# Central_Board.net
KiCad netlist of a schematic drawn in EAGLE
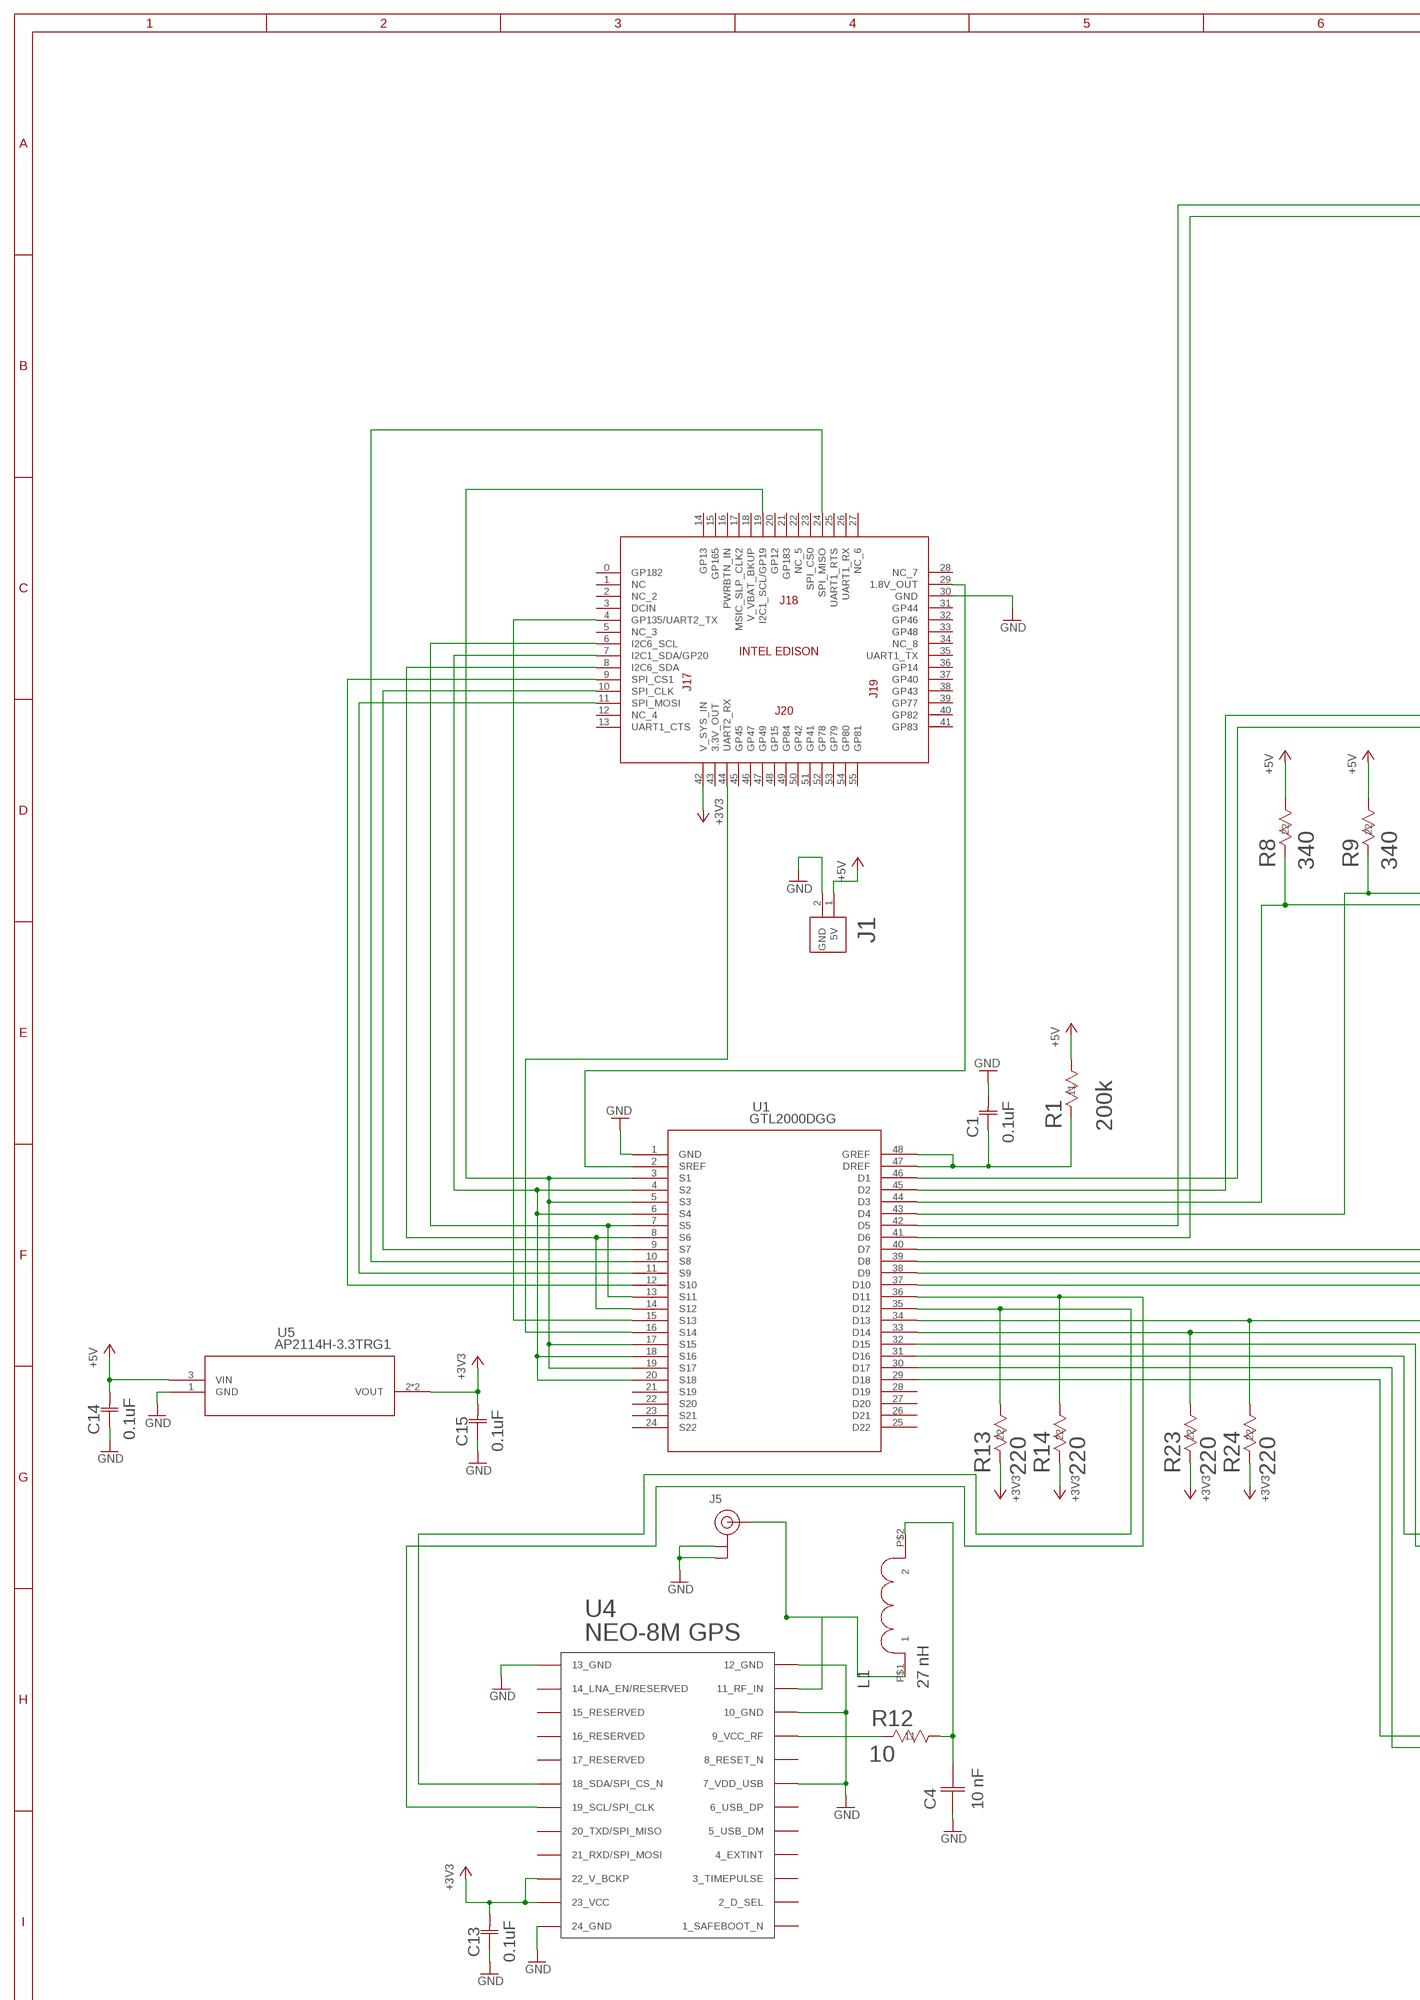
[diagram p0: schematic, sheet 1, part 1 of 2]
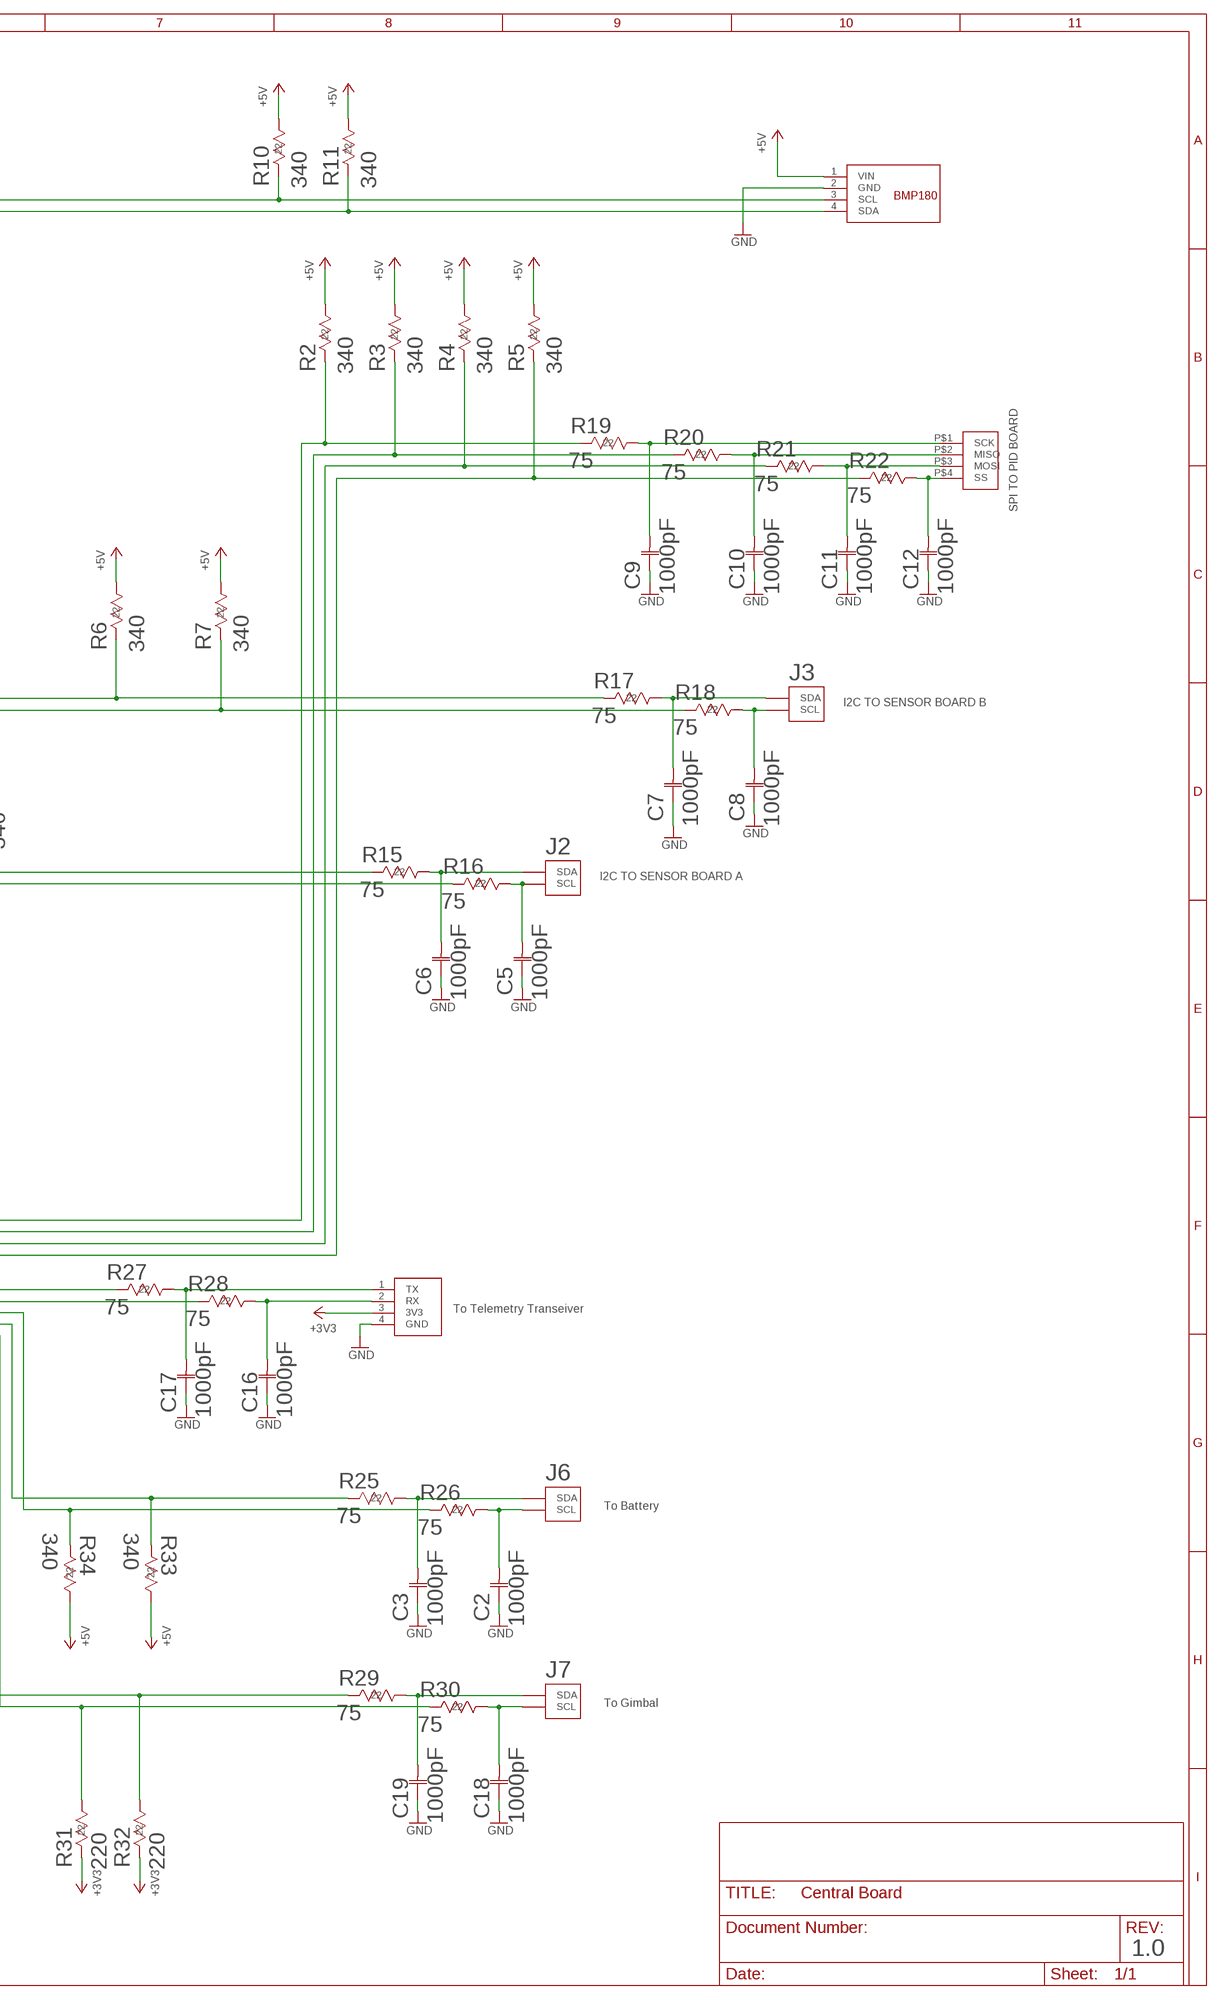
[diagram p1: schematic, sheet 1, part 2 of 2]

(export (version "E")
  (design (tool "Eeschema 10.0.6"))
  (components
    (comp (ref "C1")
      (value "0.1uF")
      (footprint "eagle-import:0805")
      (fields (field (name "MANUFACTURER_PART_NUMBER") "08055C104KAT2A"))
      (libsource (lib "eagle-import") (part "08055C104KAT2A"))
    )
    (comp (ref "C2")
      (value "1000pF")
      (footprint "eagle-import:G-155-M")
      (fields (field (name "MANUFACTURER_PART_NUMBER") "GRM155R60J102KA01D"))
      (libsource (lib "eagle-import") (part "GRM155R60J102KA01DG-155-M"))
    )
    (comp (ref "C3")
      (value "1000pF")
      (footprint "eagle-import:G-155-M")
      (fields (field (name "MANUFACTURER_PART_NUMBER") "GRM155R60J102KA01D"))
      (libsource (lib "eagle-import") (part "GRM155R60J102KA01DG-155-M"))
    )
    (comp (ref "C4")
      (value "10 nF")
      (footprint "eagle-import:0603_CAPACITOR")
      (libsource (lib "eagle-import") (part "10NF_CAPACITOR"))
    )
    (comp (ref "C5")
      (value "1000pF")
      (footprint "eagle-import:G-155-M")
      (fields (field (name "MANUFACTURER_PART_NUMBER") "GRM155R60J102KA01D"))
      (libsource (lib "eagle-import") (part "GRM155R60J102KA01DG-155-M"))
    )
    (comp (ref "C6")
      (value "1000pF")
      (footprint "eagle-import:G-155-M")
      (fields (field (name "MANUFACTURER_PART_NUMBER") "GRM155R60J102KA01D"))
      (libsource (lib "eagle-import") (part "GRM155R60J102KA01DG-155-M"))
    )
    (comp (ref "C7")
      (value "1000pF")
      (footprint "eagle-import:G-155-M")
      (fields (field (name "MANUFACTURER_PART_NUMBER") "GRM155R60J102KA01D"))
      (libsource (lib "eagle-import") (part "GRM155R60J102KA01DG-155-M"))
    )
    (comp (ref "C8")
      (value "1000pF")
      (footprint "eagle-import:G-155-M")
      (fields (field (name "MANUFACTURER_PART_NUMBER") "GRM155R60J102KA01D"))
      (libsource (lib "eagle-import") (part "GRM155R60J102KA01DG-155-M"))
    )
    (comp (ref "C9")
      (value "1000pF")
      (footprint "eagle-import:G-155-M")
      (fields (field (name "MANUFACTURER_PART_NUMBER") "GRM155R60J102KA01D"))
      (libsource (lib "eagle-import") (part "GRM155R60J102KA01DG-155-M"))
    )
    (comp (ref "C10")
      (value "1000pF")
      (footprint "eagle-import:G-155-M")
      (fields (field (name "MANUFACTURER_PART_NUMBER") "GRM155R60J102KA01D"))
      (libsource (lib "eagle-import") (part "GRM155R60J102KA01DG-155-M"))
    )
    (comp (ref "C11")
      (value "1000pF")
      (footprint "eagle-import:G-155-M")
      (fields (field (name "MANUFACTURER_PART_NUMBER") "GRM155R60J102KA01D"))
      (libsource (lib "eagle-import") (part "GRM155R60J102KA01DG-155-M"))
    )
    (comp (ref "C12")
      (value "1000pF")
      (footprint "eagle-import:G-155-M")
      (fields (field (name "MANUFACTURER_PART_NUMBER") "GRM155R60J102KA01D"))
      (libsource (lib "eagle-import") (part "GRM155R60J102KA01DG-155-M"))
    )
    (comp (ref "C13")
      (value "0.1uF")
      (footprint "eagle-import:0805")
      (fields (field (name "MANUFACTURER_PART_NUMBER") "08055C104KAT2A"))
      (libsource (lib "eagle-import") (part "08055C104KAT2A"))
    )
    (comp (ref "C14")
      (value "0.1uF")
      (footprint "eagle-import:0805")
      (fields (field (name "MANUFACTURER_PART_NUMBER") "08055C104KAT2A"))
      (libsource (lib "eagle-import") (part "08055C104KAT2A"))
    )
    (comp (ref "C15")
      (value "0.1uF")
      (footprint "eagle-import:0805")
      (fields (field (name "MANUFACTURER_PART_NUMBER") "08055C104KAT2A"))
      (libsource (lib "eagle-import") (part "08055C104KAT2A"))
    )
    (comp (ref "C16")
      (value "1000pF")
      (footprint "eagle-import:G-155-M")
      (fields (field (name "MANUFACTURER_PART_NUMBER") "GRM155R60J102KA01D"))
      (libsource (lib "eagle-import") (part "GRM155R60J102KA01DG-155-M"))
    )
    (comp (ref "C17")
      (value "1000pF")
      (footprint "eagle-import:G-155-M")
      (fields (field (name "MANUFACTURER_PART_NUMBER") "GRM155R60J102KA01D"))
      (libsource (lib "eagle-import") (part "GRM155R60J102KA01DG-155-M"))
    )
    (comp (ref "C18")
      (value "1000pF")
      (footprint "eagle-import:G-155-M")
      (fields (field (name "MANUFACTURER_PART_NUMBER") "GRM155R60J102KA01D"))
      (libsource (lib "eagle-import") (part "GRM155R60J102KA01DG-155-M"))
    )
    (comp (ref "C19")
      (value "1000pF")
      (footprint "eagle-import:G-155-M")
      (fields (field (name "MANUFACTURER_PART_NUMBER") "GRM155R60J102KA01D"))
      (libsource (lib "eagle-import") (part "GRM155R60J102KA01DG-155-M"))
    )
    (comp (ref "J1")
      (value "POWER_CONNECTOR")
      (footprint "eagle-import:XH_CONNECTOR")
      (libsource (lib "eagle-import") (part "POWER_CONNECTOR"))
    )
    (comp (ref "J2")
      (value "I2C_CONNECTOR")
      (footprint "eagle-import:XH_CONNECTOR")
      (libsource (lib "eagle-import") (part "I2C_CONNECTOR"))
    )
    (comp (ref "J3")
      (value "I2C_CONNECTOR")
      (footprint "eagle-import:XH_CONNECTOR")
      (libsource (lib "eagle-import") (part "I2C_CONNECTOR"))
    )
    (comp (ref "J4")
      (value "SPI_CONNECTOR")
      (footprint "eagle-import:JST-XH_4POS")
      (libsource (lib "eagle-import") (part "SPI_CONNECTOR"))
    )
    (comp (ref "J5")
      (value "U.FL")
      (footprint "eagle-import:U.FL")
      (libsource (lib "eagle-import") (part "U.FL"))
    )
    (comp (ref "J6")
      (value "I2C_CONNECTOR")
      (footprint "eagle-import:XH_CONNECTOR")
      (libsource (lib "eagle-import") (part "I2C_CONNECTOR"))
    )
    (comp (ref "J7")
      (value "I2C_CONNECTOR")
      (footprint "eagle-import:XH_CONNECTOR")
      (libsource (lib "eagle-import") (part "I2C_CONNECTOR"))
    )
    (comp (ref "L1")
      (value "27 nH")
      (footprint "eagle-import:0402_INDUCTOR")
      (libsource (lib "eagle-import") (part "27NH_INDUCTOR"))
    )
    (comp (ref "R1")
      (value "200k")
      (footprint "eagle-import:STA_RMCF0603")
      (fields (field (name "MANUFACTURER_PART_NUMBER") "RMCF0603FT200K"))
      (libsource (lib "eagle-import") (part "RMCF0603FT200K"))
    )
    (comp (ref "R2")
      (value "340")
      (footprint "eagle-import:RC0603N")
      (fields
        (field (name "DIGIKEYPARTNUMBER") "311340HRTRND")
        (field (name "MANUFACTURER_PART_NUMBER") "RC0603FR07340RL")
        (field (name "NEWARKPARTNUMBER") "66R2325")
      )
      (libsource (lib "eagle-import") (part "RC0603FR-07340RL"))
    )
    (comp (ref "R3")
      (value "340")
      (footprint "eagle-import:RC0603N")
      (fields
        (field (name "DIGIKEYPARTNUMBER") "311340HRTRND")
        (field (name "MANUFACTURER_PART_NUMBER") "RC0603FR07340RL")
        (field (name "NEWARKPARTNUMBER") "66R2325")
      )
      (libsource (lib "eagle-import") (part "RC0603FR-07340RL"))
    )
    (comp (ref "R4")
      (value "340")
      (footprint "eagle-import:RC0603N")
      (fields
        (field (name "DIGIKEYPARTNUMBER") "311340HRTRND")
        (field (name "MANUFACTURER_PART_NUMBER") "RC0603FR07340RL")
        (field (name "NEWARKPARTNUMBER") "66R2325")
      )
      (libsource (lib "eagle-import") (part "RC0603FR-07340RL"))
    )
    (comp (ref "R5")
      (value "340")
      (footprint "eagle-import:RC0603N")
      (fields
        (field (name "DIGIKEYPARTNUMBER") "311340HRTRND")
        (field (name "MANUFACTURER_PART_NUMBER") "RC0603FR07340RL")
        (field (name "NEWARKPARTNUMBER") "66R2325")
      )
      (libsource (lib "eagle-import") (part "RC0603FR-07340RL"))
    )
    (comp (ref "R6")
      (value "340")
      (footprint "eagle-import:RC0603N")
      (fields
        (field (name "DIGIKEYPARTNUMBER") "311340HRTRND")
        (field (name "MANUFACTURER_PART_NUMBER") "RC0603FR07340RL")
        (field (name "NEWARKPARTNUMBER") "66R2325")
      )
      (libsource (lib "eagle-import") (part "RC0603FR-07340RL"))
    )
    (comp (ref "R7")
      (value "340")
      (footprint "eagle-import:RC0603N")
      (fields
        (field (name "DIGIKEYPARTNUMBER") "311340HRTRND")
        (field (name "MANUFACTURER_PART_NUMBER") "RC0603FR07340RL")
        (field (name "NEWARKPARTNUMBER") "66R2325")
      )
      (libsource (lib "eagle-import") (part "RC0603FR-07340RL"))
    )
    (comp (ref "R8")
      (value "340")
      (footprint "eagle-import:RC0603N")
      (fields
        (field (name "DIGIKEYPARTNUMBER") "311340HRTRND")
        (field (name "MANUFACTURER_PART_NUMBER") "RC0603FR07340RL")
        (field (name "NEWARKPARTNUMBER") "66R2325")
      )
      (libsource (lib "eagle-import") (part "RC0603FR-07340RL"))
    )
    (comp (ref "R9")
      (value "340")
      (footprint "eagle-import:RC0603N")
      (fields
        (field (name "DIGIKEYPARTNUMBER") "311340HRTRND")
        (field (name "MANUFACTURER_PART_NUMBER") "RC0603FR07340RL")
        (field (name "NEWARKPARTNUMBER") "66R2325")
      )
      (libsource (lib "eagle-import") (part "RC0603FR-07340RL"))
    )
    (comp (ref "R10")
      (value "340")
      (footprint "eagle-import:RC0603N")
      (fields
        (field (name "DIGIKEYPARTNUMBER") "311340HRTRND")
        (field (name "MANUFACTURER_PART_NUMBER") "RC0603FR07340RL")
        (field (name "NEWARKPARTNUMBER") "66R2325")
      )
      (libsource (lib "eagle-import") (part "RC0603FR-07340RL"))
    )
    (comp (ref "R11")
      (value "340")
      (footprint "eagle-import:RC0603N")
      (fields
        (field (name "DIGIKEYPARTNUMBER") "311340HRTRND")
        (field (name "MANUFACTURER_PART_NUMBER") "RC0603FR07340RL")
        (field (name "NEWARKPARTNUMBER") "66R2325")
      )
      (libsource (lib "eagle-import") (part "RC0603FR-07340RL"))
    )
    (comp (ref "R12")
      (value "10")
      (footprint "eagle-import:STA_RNCP0805-M")
      (fields (field (name "MANUFACTURER_PART_NUMBER") "RNCP0805FTD10R0"))
      (libsource (lib "eagle-import") (part "RNCP0805FTD10R0STA_RNCP0805-M"))
    )
    (comp (ref "R13")
      (value "220")
      (footprint "eagle-import:RC0603N-M")
      (fields
        (field (name "DIGIKEYPARTNUMBER") "311220GRTRND")
        (field (name "MANUFACTURER_PART_NUMBER") "RC0603JR07220RL")
        (field (name "NEWARKPARTNUMBER") "68R0170")
      )
      (libsource (lib "eagle-import") (part "RC0603JR-07220RLRC0603N-M"))
    )
    (comp (ref "R14")
      (value "220")
      (footprint "eagle-import:RC0603N-M")
      (fields
        (field (name "DIGIKEYPARTNUMBER") "311220GRTRND")
        (field (name "MANUFACTURER_PART_NUMBER") "RC0603JR07220RL")
        (field (name "NEWARKPARTNUMBER") "68R0170")
      )
      (libsource (lib "eagle-import") (part "RC0603JR-07220RLRC0603N-M"))
    )
    (comp (ref "R15")
      (value "75")
      (footprint "eagle-import:RC0402N-M")
      (fields
        (field (name "DIGIKEYPARTNUMBER") "31175JRTRND")
        (field (name "MANUFACTURER_PART_NUMBER") "RC0402JR0775RL")
        (field (name "NEWARKPARTNUMBER") "66R1890")
      )
      (libsource (lib "eagle-import") (part "RC0402JR-0775RLRC0402N-M"))
    )
    (comp (ref "R16")
      (value "75")
      (footprint "eagle-import:RC0402N-M")
      (fields
        (field (name "DIGIKEYPARTNUMBER") "31175JRTRND")
        (field (name "MANUFACTURER_PART_NUMBER") "RC0402JR0775RL")
        (field (name "NEWARKPARTNUMBER") "66R1890")
      )
      (libsource (lib "eagle-import") (part "RC0402JR-0775RLRC0402N-M"))
    )
    (comp (ref "R17")
      (value "75")
      (footprint "eagle-import:RC0402N-M")
      (fields
        (field (name "DIGIKEYPARTNUMBER") "31175JRTRND")
        (field (name "MANUFACTURER_PART_NUMBER") "RC0402JR0775RL")
        (field (name "NEWARKPARTNUMBER") "66R1890")
      )
      (libsource (lib "eagle-import") (part "RC0402JR-0775RLRC0402N-M"))
    )
    (comp (ref "R18")
      (value "75")
      (footprint "eagle-import:RC0402N-M")
      (fields
        (field (name "DIGIKEYPARTNUMBER") "31175JRTRND")
        (field (name "MANUFACTURER_PART_NUMBER") "RC0402JR0775RL")
        (field (name "NEWARKPARTNUMBER") "66R1890")
      )
      (libsource (lib "eagle-import") (part "RC0402JR-0775RLRC0402N-M"))
    )
    (comp (ref "R19")
      (value "75")
      (footprint "eagle-import:RC0402N-M")
      (fields
        (field (name "DIGIKEYPARTNUMBER") "31175JRTRND")
        (field (name "MANUFACTURER_PART_NUMBER") "RC0402JR0775RL")
        (field (name "NEWARKPARTNUMBER") "66R1890")
      )
      (libsource (lib "eagle-import") (part "RC0402JR-0775RLRC0402N-M"))
    )
    (comp (ref "R20")
      (value "75")
      (footprint "eagle-import:RC0402N-M")
      (fields
        (field (name "DIGIKEYPARTNUMBER") "31175JRTRND")
        (field (name "MANUFACTURER_PART_NUMBER") "RC0402JR0775RL")
        (field (name "NEWARKPARTNUMBER") "66R1890")
      )
      (libsource (lib "eagle-import") (part "RC0402JR-0775RLRC0402N-M"))
    )
    (comp (ref "R21")
      (value "75")
      (footprint "eagle-import:RC0402N-M")
      (fields
        (field (name "DIGIKEYPARTNUMBER") "31175JRTRND")
        (field (name "MANUFACTURER_PART_NUMBER") "RC0402JR0775RL")
        (field (name "NEWARKPARTNUMBER") "66R1890")
      )
      (libsource (lib "eagle-import") (part "RC0402JR-0775RLRC0402N-M"))
    )
    (comp (ref "R22")
      (value "75")
      (footprint "eagle-import:RC0402N-M")
      (fields
        (field (name "DIGIKEYPARTNUMBER") "31175JRTRND")
        (field (name "MANUFACTURER_PART_NUMBER") "RC0402JR0775RL")
        (field (name "NEWARKPARTNUMBER") "66R1890")
      )
      (libsource (lib "eagle-import") (part "RC0402JR-0775RLRC0402N-M"))
    )
    (comp (ref "R23")
      (value "220")
      (footprint "eagle-import:RC0603N-M")
      (fields
        (field (name "DIGIKEYPARTNUMBER") "311220GRTRND")
        (field (name "MANUFACTURER_PART_NUMBER") "RC0603JR07220RL")
        (field (name "NEWARKPARTNUMBER") "68R0170")
      )
      (libsource (lib "eagle-import") (part "RC0603JR-07220RLRC0603N-M"))
    )
    (comp (ref "R24")
      (value "220")
      (footprint "eagle-import:RC0603N-M")
      (fields
        (field (name "DIGIKEYPARTNUMBER") "311220GRTRND")
        (field (name "MANUFACTURER_PART_NUMBER") "RC0603JR07220RL")
        (field (name "NEWARKPARTNUMBER") "68R0170")
      )
      (libsource (lib "eagle-import") (part "RC0603JR-07220RLRC0603N-M"))
    )
    (comp (ref "R25")
      (value "75")
      (footprint "eagle-import:RC0402N-M")
      (fields
        (field (name "DIGIKEYPARTNUMBER") "31175JRTRND")
        (field (name "MANUFACTURER_PART_NUMBER") "RC0402JR0775RL")
        (field (name "NEWARKPARTNUMBER") "66R1890")
      )
      (libsource (lib "eagle-import") (part "RC0402JR-0775RLRC0402N-M"))
    )
    (comp (ref "R26")
      (value "75")
      (footprint "eagle-import:RC0402N-M")
      (fields
        (field (name "DIGIKEYPARTNUMBER") "31175JRTRND")
        (field (name "MANUFACTURER_PART_NUMBER") "RC0402JR0775RL")
        (field (name "NEWARKPARTNUMBER") "66R1890")
      )
      (libsource (lib "eagle-import") (part "RC0402JR-0775RLRC0402N-M"))
    )
    (comp (ref "R27")
      (value "75")
      (footprint "eagle-import:RC0402N-M")
      (fields
        (field (name "DIGIKEYPARTNUMBER") "31175JRTRND")
        (field (name "MANUFACTURER_PART_NUMBER") "RC0402JR0775RL")
        (field (name "NEWARKPARTNUMBER") "66R1890")
      )
      (libsource (lib "eagle-import") (part "RC0402JR-0775RLRC0402N-M"))
    )
    (comp (ref "R28")
      (value "75")
      (footprint "eagle-import:RC0402N-M")
      (fields
        (field (name "DIGIKEYPARTNUMBER") "31175JRTRND")
        (field (name "MANUFACTURER_PART_NUMBER") "RC0402JR0775RL")
        (field (name "NEWARKPARTNUMBER") "66R1890")
      )
      (libsource (lib "eagle-import") (part "RC0402JR-0775RLRC0402N-M"))
    )
    (comp (ref "R29")
      (value "75")
      (footprint "eagle-import:RC0402N-M")
      (fields
        (field (name "DIGIKEYPARTNUMBER") "31175JRTRND")
        (field (name "MANUFACTURER_PART_NUMBER") "RC0402JR0775RL")
        (field (name "NEWARKPARTNUMBER") "66R1890")
      )
      (libsource (lib "eagle-import") (part "RC0402JR-0775RLRC0402N-M"))
    )
    (comp (ref "R30")
      (value "75")
      (footprint "eagle-import:RC0402N-M")
      (fields
        (field (name "DIGIKEYPARTNUMBER") "31175JRTRND")
        (field (name "MANUFACTURER_PART_NUMBER") "RC0402JR0775RL")
        (field (name "NEWARKPARTNUMBER") "66R1890")
      )
      (libsource (lib "eagle-import") (part "RC0402JR-0775RLRC0402N-M"))
    )
    (comp (ref "R31")
      (value "220")
      (footprint "eagle-import:RC0603N-M")
      (fields
        (field (name "DIGIKEYPARTNUMBER") "311220GRTRND")
        (field (name "MANUFACTURER_PART_NUMBER") "RC0603JR07220RL")
        (field (name "NEWARKPARTNUMBER") "68R0170")
      )
      (libsource (lib "eagle-import") (part "RC0603JR-07220RLRC0603N-M"))
    )
    (comp (ref "R32")
      (value "220")
      (footprint "eagle-import:RC0603N-M")
      (fields
        (field (name "DIGIKEYPARTNUMBER") "311220GRTRND")
        (field (name "MANUFACTURER_PART_NUMBER") "RC0603JR07220RL")
        (field (name "NEWARKPARTNUMBER") "68R0170")
      )
      (libsource (lib "eagle-import") (part "RC0603JR-07220RLRC0603N-M"))
    )
    (comp (ref "R33")
      (value "340")
      (footprint "eagle-import:RC0603N")
      (fields
        (field (name "DIGIKEYPARTNUMBER") "311340HRTRND")
        (field (name "MANUFACTURER_PART_NUMBER") "RC0603FR07340RL")
        (field (name "NEWARKPARTNUMBER") "66R2325")
      )
      (libsource (lib "eagle-import") (part "RC0603FR-07340RL"))
    )
    (comp (ref "R34")
      (value "340")
      (footprint "eagle-import:RC0603N")
      (fields
        (field (name "DIGIKEYPARTNUMBER") "311340HRTRND")
        (field (name "MANUFACTURER_PART_NUMBER") "RC0603FR07340RL")
        (field (name "NEWARKPARTNUMBER") "66R2325")
      )
      (libsource (lib "eagle-import") (part "RC0603FR-07340RL"))
    )
    (comp (ref "U$1")
      (value "4_PIN_TELE_CONNECTOR")
      (footprint "eagle-import:4_PIN_TELE_CONNECTOR")
      (libsource (lib "eagle-import") (part "4_PIN_TELE_CONNECTOR"))
    )
    (comp (ref "U1")
      (value "GTL2000DGG")
      (footprint "eagle-import:SOT362-1")
      (libsource (lib "eagle-import") (part "GTL2000DGG"))
    )
    (comp (ref "U3")
      (value "INTEL_EDISON")
      (footprint "eagle-import:INTEL_EDISON")
      (libsource (lib "eagle-import") (part "INTEL_EDISON"))
    )
    (comp (ref "U4")
      (value "NEO-M8")
      (footprint "eagle-import:NEO-M8")
      (libsource (lib "eagle-import") (part "NEO-M8"))
    )
    (comp (ref "U5")
      (value "AP2114H-3.3TRG1")
      (footprint "eagle-import:SOT-223")
      (fields (field (name "MANUFACTURER_PART_NUMBER") "ap2114h3.3trg1"))
      (libsource (lib "eagle-import") (part "AP2114H-3.3TRG1"))
    )
    (comp (ref "U9")
      (value "BMP180_BARO")
      (footprint "eagle-import:BMP180_BARO")
      (libsource (lib "eagle-import") (part "BMP180_BARO"))
    )
  )
  (nets
    (net (code "1") (name "+3V3") (class "Default")
      (node (ref "C13") (pin "2") (pinfunction "2_2") (pintype "passive"))
      (node (ref "C15") (pin "2") (pinfunction "2_2") (pintype "passive"))
      (node (ref "R13") (pin "2") (pinfunction "22_2") (pintype "passive"))
      (node (ref "R14") (pin "2") (pinfunction "22_2") (pintype "passive"))
      (node (ref "R23") (pin "2") (pinfunction "22_2") (pintype "passive"))
      (node (ref "R24") (pin "2") (pinfunction "22_2") (pintype "passive"))
      (node (ref "R31") (pin "2") (pinfunction "22_2") (pintype "passive"))
      (node (ref "R32") (pin "2") (pinfunction "22_2") (pintype "passive"))
      (node (ref "U$1") (pin "3") (pinfunction "3V3_3") (pintype "bidirectional"))
      (node (ref "U3") (pin "42") (pinfunction "V_SYS_IN_42") (pintype "power_in"))
      (node (ref "U4") (pin "22") (pinfunction "22_V_BCKP_22") (pintype "bidirectional"))
      (node (ref "U4") (pin "23") (pinfunction "23_VCC_23") (pintype "bidirectional"))
      (node (ref "U5") (pin "2") (pinfunction "VOUT_2") (pintype "output"))
      (node (ref "U5") (pin "4") (pinfunction "VOUT_4") (pintype "output"))
    )
    (net (code "2") (name "+5V") (class "Default")
      (node (ref "C14") (pin "2") (pinfunction "2_2") (pintype "passive"))
      (node (ref "J1") (pin "1") (pinfunction "5V_1") (pintype "power_in"))
      (node (ref "R1") (pin "2") (pinfunction "22_2") (pintype "passive"))
      (node (ref "R10") (pin "1") (pinfunction "11_1") (pintype "passive"))
      (node (ref "R11") (pin "1") (pinfunction "11_1") (pintype "passive"))
      (node (ref "R2") (pin "1") (pinfunction "11_1") (pintype "passive"))
      (node (ref "R3") (pin "1") (pinfunction "11_1") (pintype "passive"))
      (node (ref "R33") (pin "1") (pinfunction "11_1") (pintype "passive"))
      (node (ref "R34") (pin "1") (pinfunction "11_1") (pintype "passive"))
      (node (ref "R4") (pin "1") (pinfunction "11_1") (pintype "passive"))
      (node (ref "R5") (pin "1") (pinfunction "11_1") (pintype "passive"))
      (node (ref "R6") (pin "1") (pinfunction "11_1") (pintype "passive"))
      (node (ref "R7") (pin "1") (pinfunction "11_1") (pintype "passive"))
      (node (ref "R8") (pin "1") (pinfunction "11_1") (pintype "passive"))
      (node (ref "R9") (pin "1") (pinfunction "11_1") (pintype "passive"))
      (node (ref "U5") (pin "3") (pinfunction "VIN_3") (pintype "input"))
      (node (ref "U9") (pin "1") (pinfunction "VIN_1") (pintype "power_in"))
    )
    (net (code "3") (name "/3.3V_OUT") (class "Default")
      (node (ref "U3") (pin "43") (pinfunction "3.3V_OUT_43") (pintype "power_in"))
    )
    (net (code "4") (name "/DCIN") (class "Default")
      (node (ref "U3") (pin "3") (pinfunction "DCIN_3") (pintype "power_in"))
    )
    (net (code "5") (name "/MSIC_SLP_CLK2") (class "Default")
      (node (ref "U3") (pin "17") (pinfunction "MSIC_SLP_CLK2_17") (pintype "power_in"))
    )
    (net (code "6") (name "/PWRBTN_IN") (class "Default")
      (node (ref "U3") (pin "16") (pinfunction "PWRBTN_IN_16") (pintype "power_in"))
    )
    (net (code "7") (name "/V_VBAT_BKUP") (class "Default")
      (node (ref "U3") (pin "18") (pinfunction "V_VBAT_BKUP_18") (pintype "power_in"))
    )
    (net (code "8") (name "GND") (class "Default")
      (node (ref "C1") (pin "2") (pinfunction "2_2") (pintype "passive"))
      (node (ref "C10") (pin "1") (pinfunction "11_1") (pintype "passive"))
      (node (ref "C11") (pin "1") (pinfunction "11_1") (pintype "passive"))
      (node (ref "C12") (pin "1") (pinfunction "11_1") (pintype "passive"))
      (node (ref "C13") (pin "1") (pinfunction "1_1") (pintype "passive"))
      (node (ref "C14") (pin "1") (pinfunction "1_1") (pintype "passive"))
      (node (ref "C15") (pin "1") (pinfunction "1_1") (pintype "passive"))
      (node (ref "C16") (pin "1") (pinfunction "11_1") (pintype "passive"))
      (node (ref "C17") (pin "1") (pinfunction "11_1") (pintype "passive"))
      (node (ref "C18") (pin "1") (pinfunction "11_1") (pintype "passive"))
      (node (ref "C19") (pin "1") (pinfunction "11_1") (pintype "passive"))
      (node (ref "C2") (pin "1") (pinfunction "11_1") (pintype "passive"))
      (node (ref "C3") (pin "1") (pinfunction "11_1") (pintype "passive"))
      (node (ref "C4") (pin "1") (pinfunction "1_1") (pintype "bidirectional"))
      (node (ref "C5") (pin "1") (pinfunction "11_1") (pintype "passive"))
      (node (ref "C6") (pin "1") (pinfunction "11_1") (pintype "passive"))
      (node (ref "C7") (pin "1") (pinfunction "11_1") (pintype "passive"))
      (node (ref "C8") (pin "1") (pinfunction "11_1") (pintype "passive"))
      (node (ref "C9") (pin "1") (pinfunction "11_1") (pintype "passive"))
      (node (ref "J1") (pin "2") (pinfunction "GND_2") (pintype "power_in"))
      (node (ref "J5") (pin "P$1") (pinfunction "GND_P$1") (pintype "bidirectional"))
      (node (ref "J5") (pin "P$2") (pinfunction "GND_P$2") (pintype "bidirectional"))
      (node (ref "U$1") (pin "4") (pinfunction "GND_4") (pintype "bidirectional"))
      (node (ref "U1") (pin "1") (pinfunction "GND_1") (pintype "passive"))
      (node (ref "U3") (pin "30") (pinfunction "GND_30") (pintype "power_in"))
      (node (ref "U4") (pin "10") (pinfunction "10_GND_10") (pintype "bidirectional"))
      (node (ref "U4") (pin "12") (pinfunction "12_GND_12") (pintype "bidirectional"))
      (node (ref "U4") (pin "13") (pinfunction "13_GND_13") (pintype "bidirectional"))
      (node (ref "U4") (pin "24") (pinfunction "24_GND_24") (pintype "bidirectional"))
      (node (ref "U4") (pin "7") (pinfunction "7_VDD_USB_7") (pintype "bidirectional"))
      (node (ref "U5") (pin "1") (pinfunction "GND_1") (pintype "power_in"))
      (node (ref "U9") (pin "2") (pinfunction "GND_2") (pintype "power_in"))
    )
    (net (code "9") (name "Net-(C2-22)") (class "Default")
      (node (ref "C2") (pin "2") (pinfunction "22_2") (pintype "passive"))
      (node (ref "J6") (pin "1") (pinfunction "SCL_1") (pintype "bidirectional"))
      (node (ref "R26") (pin "1") (pinfunction "11_1") (pintype "passive"))
    )
    (net (code "10") (name "Net-(C3-22)") (class "Default")
      (node (ref "C3") (pin "2") (pinfunction "22_2") (pintype "passive"))
      (node (ref "J6") (pin "2") (pinfunction "SDA_2") (pintype "bidirectional"))
      (node (ref "R25") (pin "1") (pinfunction "11_1") (pintype "passive"))
    )
    (net (code "11") (name "Net-(C5-22)") (class "Default")
      (node (ref "C5") (pin "2") (pinfunction "22_2") (pintype "passive"))
      (node (ref "J2") (pin "1") (pinfunction "SCL_1") (pintype "bidirectional"))
      (node (ref "R16") (pin "1") (pinfunction "11_1") (pintype "passive"))
    )
    (net (code "12") (name "Net-(C6-22)") (class "Default")
      (node (ref "C6") (pin "2") (pinfunction "22_2") (pintype "passive"))
      (node (ref "J2") (pin "2") (pinfunction "SDA_2") (pintype "bidirectional"))
      (node (ref "R15") (pin "1") (pinfunction "11_1") (pintype "passive"))
    )
    (net (code "13") (name "Net-(C7-22)") (class "Default")
      (node (ref "C7") (pin "2") (pinfunction "22_2") (pintype "passive"))
      (node (ref "J3") (pin "2") (pinfunction "SDA_2") (pintype "bidirectional"))
      (node (ref "R17") (pin "1") (pinfunction "11_1") (pintype "passive"))
    )
    (net (code "14") (name "Net-(C8-22)") (class "Default")
      (node (ref "C8") (pin "2") (pinfunction "22_2") (pintype "passive"))
      (node (ref "J3") (pin "1") (pinfunction "SCL_1") (pintype "bidirectional"))
      (node (ref "R18") (pin "1") (pinfunction "11_1") (pintype "passive"))
    )
    (net (code "15") (name "Net-(C9-22)") (class "Default")
      (node (ref "C9") (pin "2") (pinfunction "22_2") (pintype "passive"))
      (node (ref "J4") (pin "P$1") (pinfunction "SCK_P$1") (pintype "bidirectional"))
      (node (ref "R19") (pin "1") (pinfunction "11_1") (pintype "passive"))
    )
    (net (code "16") (name "Net-(C10-22)") (class "Default")
      (node (ref "C10") (pin "2") (pinfunction "22_2") (pintype "passive"))
      (node (ref "J4") (pin "P$2") (pinfunction "MISO_P$2") (pintype "bidirectional"))
      (node (ref "R20") (pin "1") (pinfunction "11_1") (pintype "passive"))
    )
    (net (code "17") (name "Net-(C11-22)") (class "Default")
      (node (ref "C11") (pin "2") (pinfunction "22_2") (pintype "passive"))
      (node (ref "J4") (pin "P$3") (pinfunction "MOSI_P$3") (pintype "bidirectional"))
      (node (ref "R21") (pin "1") (pinfunction "11_1") (pintype "passive"))
    )
    (net (code "18") (name "Net-(C12-22)") (class "Default")
      (node (ref "C12") (pin "2") (pinfunction "22_2") (pintype "passive"))
      (node (ref "J4") (pin "P$4") (pinfunction "SS_P$4") (pintype "bidirectional"))
      (node (ref "R22") (pin "1") (pinfunction "11_1") (pintype "passive"))
    )
    (net (code "19") (name "Net-(C16-22)") (class "Default")
      (node (ref "C16") (pin "2") (pinfunction "22_2") (pintype "passive"))
      (node (ref "R28") (pin "1") (pinfunction "11_1") (pintype "passive"))
      (node (ref "U$1") (pin "2") (pinfunction "RX_2") (pintype "bidirectional"))
    )
    (net (code "20") (name "Net-(C17-22)") (class "Default")
      (node (ref "C17") (pin "2") (pinfunction "22_2") (pintype "passive"))
      (node (ref "R27") (pin "1") (pinfunction "11_1") (pintype "passive"))
      (node (ref "U$1") (pin "1") (pinfunction "TX_1") (pintype "bidirectional"))
    )
    (net (code "21") (name "Net-(C18-22)") (class "Default")
      (node (ref "C18") (pin "2") (pinfunction "22_2") (pintype "passive"))
      (node (ref "J7") (pin "1") (pinfunction "SCL_1") (pintype "bidirectional"))
      (node (ref "R30") (pin "1") (pinfunction "11_1") (pintype "passive"))
    )
    (net (code "22") (name "Net-(C19-22)") (class "Default")
      (node (ref "C19") (pin "2") (pinfunction "22_2") (pintype "passive"))
      (node (ref "J7") (pin "2") (pinfunction "SDA_2") (pintype "bidirectional"))
      (node (ref "R29") (pin "1") (pinfunction "11_1") (pintype "passive"))
    )
    (net (code "23") (name "Net-(J5-SIGNAL)") (class "Default")
      (node (ref "J5") (pin "P$3") (pinfunction "SIGNAL_P$3") (pintype "bidirectional"))
      (node (ref "L1") (pin "P$1") (pinfunction "1_P$1") (pintype "passive"))
      (node (ref "U4") (pin "11") (pinfunction "11_RF_IN_11") (pintype "bidirectional"))
    )
    (net (code "24") (name "Net-(L1-2)") (class "Default")
      (node (ref "C4") (pin "2") (pinfunction "2_2") (pintype "bidirectional"))
      (node (ref "L1") (pin "P$2") (pinfunction "2_P$2") (pintype "passive"))
      (node (ref "R12") (pin "2") (pinfunction "22_2") (pintype "passive"))
    )
    (net (code "25") (name "Net-(R1-11)") (class "Default")
      (node (ref "C1") (pin "1") (pinfunction "1_1") (pintype "passive"))
      (node (ref "R1") (pin "1") (pinfunction "11_1") (pintype "passive"))
      (node (ref "U1") (pin "47") (pinfunction "DREF_47") (pintype "passive"))
      (node (ref "U1") (pin "48") (pinfunction "GREF_48") (pintype "passive"))
    )
    (net (code "26") (name "Net-(R10-22)") (class "Default")
      (node (ref "R10") (pin "2") (pinfunction "22_2") (pintype "passive"))
      (node (ref "U1") (pin "42") (pinfunction "D5_42") (pintype "passive"))
      (node (ref "U9") (pin "3") (pinfunction "SCL_3") (pintype "bidirectional"))
    )
    (net (code "27") (name "Net-(R11-22)") (class "Default")
      (node (ref "R11") (pin "2") (pinfunction "22_2") (pintype "passive"))
      (node (ref "U1") (pin "41") (pinfunction "D6_41") (pintype "passive"))
      (node (ref "U9") (pin "4") (pinfunction "SDA_4") (pintype "bidirectional"))
    )
    (net (code "28") (name "Net-(R12-11)") (class "Default")
      (node (ref "R12") (pin "1") (pinfunction "11_1") (pintype "passive"))
      (node (ref "U4") (pin "9") (pinfunction "9_VCC_RF_9") (pintype "bidirectional"))
    )
    (net (code "29") (name "Net-(R13-11)") (class "Default")
      (node (ref "R13") (pin "1") (pinfunction "11_1") (pintype "passive"))
      (node (ref "U1") (pin "35") (pinfunction "D12_35") (pintype "passive"))
      (node (ref "U4") (pin "18") (pinfunction "18_SDA/SPI_CS_N_18") (pintype "bidirectional"))
    )
    (net (code "30") (name "Net-(R14-11)") (class "Default")
      (node (ref "R14") (pin "1") (pinfunction "11_1") (pintype "passive"))
      (node (ref "U1") (pin "36") (pinfunction "D11_36") (pintype "passive"))
      (node (ref "U4") (pin "19") (pinfunction "19_SCL/SPI_CLK_19") (pintype "bidirectional"))
    )
    (net (code "31") (name "Net-(R15-22)") (class "Default")
      (node (ref "R15") (pin "2") (pinfunction "22_2") (pintype "passive"))
      (node (ref "R9") (pin "2") (pinfunction "22_2") (pintype "passive"))
      (node (ref "U1") (pin "43") (pinfunction "D4_43") (pintype "passive"))
    )
    (net (code "32") (name "Net-(R16-22)") (class "Default")
      (node (ref "R16") (pin "2") (pinfunction "22_2") (pintype "passive"))
      (node (ref "R8") (pin "2") (pinfunction "22_2") (pintype "passive"))
      (node (ref "U1") (pin "44") (pinfunction "D3_44") (pintype "passive"))
    )
    (net (code "33") (name "Net-(R17-22)") (class "Default")
      (node (ref "R17") (pin "2") (pinfunction "22_2") (pintype "passive"))
      (node (ref "R6") (pin "2") (pinfunction "22_2") (pintype "passive"))
      (node (ref "U1") (pin "45") (pinfunction "D2_45") (pintype "passive"))
    )
    (net (code "34") (name "Net-(R18-22)") (class "Default")
      (node (ref "R18") (pin "2") (pinfunction "22_2") (pintype "passive"))
      (node (ref "R7") (pin "2") (pinfunction "22_2") (pintype "passive"))
      (node (ref "U1") (pin "46") (pinfunction "D1_46") (pintype "passive"))
    )
    (net (code "35") (name "Net-(R19-22)") (class "Default")
      (node (ref "R19") (pin "2") (pinfunction "22_2") (pintype "passive"))
      (node (ref "R2") (pin "2") (pinfunction "22_2") (pintype "passive"))
      (node (ref "U1") (pin "40") (pinfunction "D7_40") (pintype "passive"))
    )
    (net (code "36") (name "Net-(R20-22)") (class "Default")
      (node (ref "R20") (pin "2") (pinfunction "22_2") (pintype "passive"))
      (node (ref "R3") (pin "2") (pinfunction "22_2") (pintype "passive"))
      (node (ref "U1") (pin "39") (pinfunction "D8_39") (pintype "passive"))
    )
    (net (code "37") (name "Net-(R21-22)") (class "Default")
      (node (ref "R21") (pin "2") (pinfunction "22_2") (pintype "passive"))
      (node (ref "R4") (pin "2") (pinfunction "22_2") (pintype "passive"))
      (node (ref "U1") (pin "38") (pinfunction "D9_38") (pintype "passive"))
    )
    (net (code "38") (name "Net-(R22-22)") (class "Default")
      (node (ref "R22") (pin "2") (pinfunction "22_2") (pintype "passive"))
      (node (ref "R5") (pin "2") (pinfunction "22_2") (pintype "passive"))
      (node (ref "U1") (pin "37") (pinfunction "D10_37") (pintype "passive"))
    )
    (net (code "39") (name "Net-(R23-11)") (class "Default")
      (node (ref "R23") (pin "1") (pinfunction "11_1") (pintype "passive"))
      (node (ref "R28") (pin "2") (pinfunction "22_2") (pintype "passive"))
      (node (ref "U1") (pin "33") (pinfunction "D14_33") (pintype "passive"))
    )
    (net (code "40") (name "Net-(R24-11)") (class "Default")
      (node (ref "R24") (pin "1") (pinfunction "11_1") (pintype "passive"))
      (node (ref "R27") (pin "2") (pinfunction "22_2") (pintype "passive"))
      (node (ref "U1") (pin "34") (pinfunction "D13_34") (pintype "passive"))
    )
    (net (code "41") (name "Net-(R25-22)") (class "Default")
      (node (ref "R25") (pin "2") (pinfunction "22_2") (pintype "passive"))
      (node (ref "R33") (pin "2") (pinfunction "22_2") (pintype "passive"))
      (node (ref "U1") (pin "31") (pinfunction "D16_31") (pintype "passive"))
    )
    (net (code "42") (name "Net-(R26-22)") (class "Default")
      (node (ref "R26") (pin "2") (pinfunction "22_2") (pintype "passive"))
      (node (ref "R34") (pin "2") (pinfunction "22_2") (pintype "passive"))
      (node (ref "U1") (pin "32") (pinfunction "D15_32") (pintype "passive"))
    )
    (net (code "43") (name "Net-(R29-22)") (class "Default")
      (node (ref "R29") (pin "2") (pinfunction "22_2") (pintype "passive"))
      (node (ref "R32") (pin "1") (pinfunction "11_1") (pintype "passive"))
      (node (ref "U1") (pin "29") (pinfunction "D18_29") (pintype "passive"))
    )
    (net (code "44") (name "Net-(R30-22)") (class "Default")
      (node (ref "R30") (pin "2") (pinfunction "22_2") (pintype "passive"))
      (node (ref "R31") (pin "1") (pinfunction "11_1") (pintype "passive"))
      (node (ref "U1") (pin "30") (pinfunction "D17_30") (pintype "passive"))
    )
    (net (code "45") (name "Net-(U1-S1)") (class "Default")
      (node (ref "U1") (pin "17") (pinfunction "S15_17") (pintype "passive"))
      (node (ref "U1") (pin "19") (pinfunction "S17_19") (pintype "passive"))
      (node (ref "U1") (pin "3") (pinfunction "S1_3") (pintype "passive"))
      (node (ref "U1") (pin "5") (pinfunction "S3_5") (pintype "passive"))
      (node (ref "U3") (pin "19") (pinfunction "I2C1_SCL/GP19_19") (pintype "bidirectional"))
    )
    (net (code "46") (name "Net-(U1-S7)") (class "Default")
      (node (ref "U1") (pin "9") (pinfunction "S7_9") (pintype "passive"))
      (node (ref "U3") (pin "10") (pinfunction "SPI_CLK_10") (pintype "bidirectional"))
    )
    (net (code "47") (name "Net-(U1-S8)") (class "Default")
      (node (ref "U1") (pin "10") (pinfunction "S8_10") (pintype "passive"))
      (node (ref "U3") (pin "24") (pinfunction "SPI_MISO_24") (pintype "bidirectional"))
    )
    (net (code "48") (name "Net-(U1-S9)") (class "Default")
      (node (ref "U1") (pin "11") (pinfunction "S9_11") (pintype "passive"))
      (node (ref "U3") (pin "11") (pinfunction "SPI_MOSI_11") (pintype "bidirectional"))
    )
    (net (code "49") (name "Net-(U1-S10)") (class "Default")
      (node (ref "U1") (pin "12") (pinfunction "S10_12") (pintype "passive"))
      (node (ref "U3") (pin "9") (pinfunction "SPI_CS1_9") (pintype "bidirectional"))
    )
    (net (code "50") (name "Net-(U1-S11)") (class "Default")
      (node (ref "U1") (pin "13") (pinfunction "S11_13") (pintype "passive"))
      (node (ref "U1") (pin "7") (pinfunction "S5_7") (pintype "passive"))
      (node (ref "U3") (pin "6") (pinfunction "I2C6_SCL_6") (pintype "bidirectional"))
    )
    (net (code "51") (name "Net-(U1-S12)") (class "Default")
      (node (ref "U1") (pin "14") (pinfunction "S12_14") (pintype "passive"))
      (node (ref "U1") (pin "8") (pinfunction "S6_8") (pintype "passive"))
      (node (ref "U3") (pin "8") (pinfunction "I2C6_SDA_8") (pintype "bidirectional"))
    )
    (net (code "52") (name "Net-(U1-S13)") (class "Default")
      (node (ref "U1") (pin "15") (pinfunction "S13_15") (pintype "passive"))
      (node (ref "U3") (pin "4") (pinfunction "GP135/UART2_TX_4") (pintype "bidirectional"))
    )
    (net (code "53") (name "Net-(U1-S14)") (class "Default")
      (node (ref "U1") (pin "16") (pinfunction "S14_16") (pintype "passive"))
      (node (ref "U3") (pin "44") (pinfunction "UART2_RX_44") (pintype "bidirectional"))
    )
    (net (code "54") (name "Net-(U1-S16)") (class "Default")
      (node (ref "U1") (pin "18") (pinfunction "S16_18") (pintype "passive"))
      (node (ref "U1") (pin "20") (pinfunction "S18_20") (pintype "passive"))
      (node (ref "U1") (pin "4") (pinfunction "S2_4") (pintype "passive"))
      (node (ref "U1") (pin "6") (pinfunction "S4_6") (pintype "passive"))
      (node (ref "U3") (pin "7") (pinfunction "I2C1_SDA/GP20_7") (pintype "bidirectional"))
    )
    (net (code "55") (name "Net-(U1-SREF)") (class "Default")
      (node (ref "U1") (pin "2") (pinfunction "SREF_2") (pintype "passive"))
      (node (ref "U3") (pin "29") (pinfunction "1.8V_OUT_29") (pintype "power_in"))
    )
    (net (code "56") (name "unconnected-(U1-D19-Pad28)") (class "Default")
      (node (ref "U1") (pin "28") (pinfunction "D19_28") (pintype "passive"))
    )
    (net (code "57") (name "unconnected-(U1-D20-Pad27)") (class "Default")
      (node (ref "U1") (pin "27") (pinfunction "D20_27") (pintype "passive"))
    )
    (net (code "58") (name "unconnected-(U1-D21-Pad26)") (class "Default")
      (node (ref "U1") (pin "26") (pinfunction "D21_26") (pintype "passive"))
    )
    (net (code "59") (name "unconnected-(U1-D22-Pad25)") (class "Default")
      (node (ref "U1") (pin "25") (pinfunction "D22_25") (pintype "passive"))
    )
    (net (code "60") (name "unconnected-(U1-S19-Pad21)") (class "Default")
      (node (ref "U1") (pin "21") (pinfunction "S19_21") (pintype "passive"))
    )
    (net (code "61") (name "unconnected-(U1-S20-Pad22)") (class "Default")
      (node (ref "U1") (pin "22") (pinfunction "S20_22") (pintype "passive"))
    )
    (net (code "62") (name "unconnected-(U1-S21-Pad23)") (class "Default")
      (node (ref "U1") (pin "23") (pinfunction "S21_23") (pintype "passive"))
    )
    (net (code "63") (name "unconnected-(U1-S22-Pad24)") (class "Default")
      (node (ref "U1") (pin "24") (pinfunction "S22_24") (pintype "passive"))
    )
    (net (code "64") (name "unconnected-(U3-GP12-Pad20)") (class "Default")
      (node (ref "U3") (pin "20") (pinfunction "GP12_20") (pintype "bidirectional"))
    )
    (net (code "65") (name "unconnected-(U3-GP13-Pad14)") (class "Default")
      (node (ref "U3") (pin "14") (pinfunction "GP13_14") (pintype "bidirectional"))
    )
    (net (code "66") (name "unconnected-(U3-GP14-Pad36)") (class "Default")
      (node (ref "U3") (pin "36") (pinfunction "GP14_36") (pintype "bidirectional"))
    )
    (net (code "67") (name "unconnected-(U3-GP15-Pad48)") (class "Default")
      (node (ref "U3") (pin "48") (pinfunction "GP15_48") (pintype "bidirectional"))
    )
    (net (code "68") (name "unconnected-(U3-GP40-Pad37)") (class "Default")
      (node (ref "U3") (pin "37") (pinfunction "GP40_37") (pintype "bidirectional"))
    )
    (net (code "69") (name "unconnected-(U3-GP41-Pad51)") (class "Default")
      (node (ref "U3") (pin "51") (pinfunction "GP41_51") (pintype "bidirectional"))
    )
    (net (code "70") (name "unconnected-(U3-GP42-Pad50)") (class "Default")
      (node (ref "U3") (pin "50") (pinfunction "GP42_50") (pintype "bidirectional"))
    )
    (net (code "71") (name "unconnected-(U3-GP43-Pad38)") (class "Default")
      (node (ref "U3") (pin "38") (pinfunction "GP43_38") (pintype "bidirectional"))
    )
    (net (code "72") (name "unconnected-(U3-GP44-Pad31)") (class "Default")
      (node (ref "U3") (pin "31") (pinfunction "GP44_31") (pintype "bidirectional"))
    )
    (net (code "73") (name "unconnected-(U3-GP45-Pad45)") (class "Default")
      (node (ref "U3") (pin "45") (pinfunction "GP45_45") (pintype "bidirectional"))
    )
    (net (code "74") (name "unconnected-(U3-GP46-Pad32)") (class "Default")
      (node (ref "U3") (pin "32") (pinfunction "GP46_32") (pintype "bidirectional"))
    )
    (net (code "75") (name "unconnected-(U3-GP47-Pad46)") (class "Default")
      (node (ref "U3") (pin "46") (pinfunction "GP47_46") (pintype "bidirectional"))
    )
    (net (code "76") (name "unconnected-(U3-GP48-Pad33)") (class "Default")
      (node (ref "U3") (pin "33") (pinfunction "GP48_33") (pintype "bidirectional"))
    )
    (net (code "77") (name "unconnected-(U3-GP49-Pad47)") (class "Default")
      (node (ref "U3") (pin "47") (pinfunction "GP49_47") (pintype "bidirectional"))
    )
    (net (code "78") (name "unconnected-(U3-GP77-Pad39)") (class "Default")
      (node (ref "U3") (pin "39") (pinfunction "GP77_39") (pintype "bidirectional"))
    )
    (net (code "79") (name "unconnected-(U3-GP78-Pad52)") (class "Default")
      (node (ref "U3") (pin "52") (pinfunction "GP78_52") (pintype "bidirectional"))
    )
    (net (code "80") (name "unconnected-(U3-GP79-Pad53)") (class "Default")
      (node (ref "U3") (pin "53") (pinfunction "GP79_53") (pintype "bidirectional"))
    )
    (net (code "81") (name "unconnected-(U3-GP80-Pad54)") (class "Default")
      (node (ref "U3") (pin "54") (pinfunction "GP80_54") (pintype "bidirectional"))
    )
    (net (code "82") (name "unconnected-(U3-GP81-Pad55)") (class "Default")
      (node (ref "U3") (pin "55") (pinfunction "GP81_55") (pintype "bidirectional"))
    )
    (net (code "83") (name "unconnected-(U3-GP82-Pad40)") (class "Default")
      (node (ref "U3") (pin "40") (pinfunction "GP82_40") (pintype "bidirectional"))
    )
    (net (code "84") (name "unconnected-(U3-GP83-Pad41)") (class "Default")
      (node (ref "U3") (pin "41") (pinfunction "GP83_41") (pintype "bidirectional"))
    )
    (net (code "85") (name "unconnected-(U3-GP84-Pad49)") (class "Default")
      (node (ref "U3") (pin "49") (pinfunction "GP84_49") (pintype "bidirectional"))
    )
    (net (code "86") (name "unconnected-(U3-GP165-Pad15)") (class "Default")
      (node (ref "U3") (pin "15") (pinfunction "GP165_15") (pintype "bidirectional"))
    )
    (net (code "87") (name "unconnected-(U3-GP182-Pad0)") (class "Default")
      (node (ref "U3") (pin "0") (pinfunction "GP182_0") (pintype "bidirectional"))
    )
    (net (code "88") (name "unconnected-(U3-GP183-Pad21)") (class "Default")
      (node (ref "U3") (pin "21") (pinfunction "GP183_21") (pintype "bidirectional"))
    )
    (net (code "89") (name "unconnected-(U3-NC-Pad1)") (class "Default")
      (node (ref "U3") (pin "1") (pinfunction "NC_1") (pintype "no_connect"))
    )
    (net (code "90") (name "unconnected-(U3-NC_2-Pad2)") (class "Default")
      (node (ref "U3") (pin "2") (pinfunction "NC_2_2") (pintype "no_connect"))
    )
    (net (code "91") (name "unconnected-(U3-NC_3-Pad5)") (class "Default")
      (node (ref "U3") (pin "5") (pinfunction "NC_3_5") (pintype "no_connect"))
    )
    (net (code "92") (name "unconnected-(U3-NC_4-Pad12)") (class "Default")
      (node (ref "U3") (pin "12") (pinfunction "NC_4_12") (pintype "no_connect"))
    )
    (net (code "93") (name "unconnected-(U3-NC_5-Pad22)") (class "Default")
      (node (ref "U3") (pin "22") (pinfunction "NC_5_22") (pintype "no_connect"))
    )
    (net (code "94") (name "unconnected-(U3-NC_6-Pad27)") (class "Default")
      (node (ref "U3") (pin "27") (pinfunction "NC_6_27") (pintype "no_connect"))
    )
    (net (code "95") (name "unconnected-(U3-NC_7-Pad28)") (class "Default")
      (node (ref "U3") (pin "28") (pinfunction "NC_7_28") (pintype "no_connect"))
    )
    (net (code "96") (name "unconnected-(U3-NC_8-Pad34)") (class "Default")
      (node (ref "U3") (pin "34") (pinfunction "NC_8_34") (pintype "no_connect"))
    )
    (net (code "97") (name "unconnected-(U3-SPI_CS0-Pad23)") (class "Default")
      (node (ref "U3") (pin "23") (pinfunction "SPI_CS0_23") (pintype "bidirectional"))
    )
    (net (code "98") (name "unconnected-(U3-UART1_CTS-Pad13)") (class "Default")
      (node (ref "U3") (pin "13") (pinfunction "UART1_CTS_13") (pintype "bidirectional"))
    )
    (net (code "99") (name "unconnected-(U3-UART1_RTS-Pad25)") (class "Default")
      (node (ref "U3") (pin "25") (pinfunction "UART1_RTS_25") (pintype "bidirectional"))
    )
    (net (code "100") (name "unconnected-(U3-UART1_RX-Pad26)") (class "Default")
      (node (ref "U3") (pin "26") (pinfunction "UART1_RX_26") (pintype "bidirectional"))
    )
    (net (code "101") (name "unconnected-(U3-UART1_TX-Pad35)") (class "Default")
      (node (ref "U3") (pin "35") (pinfunction "UART1_TX_35") (pintype "bidirectional"))
    )
    (net (code "102") (name "unconnected-(U4-1_SAFEBOOT_N-Pad1)") (class "Default")
      (node (ref "U4") (pin "1") (pinfunction "1_SAFEBOOT_N_1") (pintype "bidirectional"))
    )
    (net (code "103") (name "unconnected-(U4-2_D_SEL-Pad2)") (class "Default")
      (node (ref "U4") (pin "2") (pinfunction "2_D_SEL_2") (pintype "bidirectional"))
    )
    (net (code "104") (name "unconnected-(U4-3_TIMEPULSE-Pad3)") (class "Default")
      (node (ref "U4") (pin "3") (pinfunction "3_TIMEPULSE_3") (pintype "bidirectional"))
    )
    (net (code "105") (name "unconnected-(U4-4_EXTINT-Pad4)") (class "Default")
      (node (ref "U4") (pin "4") (pinfunction "4_EXTINT_4") (pintype "bidirectional"))
    )
    (net (code "106") (name "unconnected-(U4-5_USB_DM-Pad5)") (class "Default")
      (node (ref "U4") (pin "5") (pinfunction "5_USB_DM_5") (pintype "bidirectional"))
    )
    (net (code "107") (name "unconnected-(U4-6_USB_DP-Pad6)") (class "Default")
      (node (ref "U4") (pin "6") (pinfunction "6_USB_DP_6") (pintype "bidirectional"))
    )
    (net (code "108") (name "unconnected-(U4-8_RESET_N-Pad8)") (class "Default")
      (node (ref "U4") (pin "8") (pinfunction "8_RESET_N_8") (pintype "bidirectional"))
    )
    (net (code "109") (name "unconnected-(U4-14_LNA_EN{slash}RESERVED-Pad14)") (class "Default")
      (node (ref "U4") (pin "14") (pinfunction "14_LNA_EN/RESERVED_14") (pintype "bidirectional"))
    )
    (net (code "110") (name "unconnected-(U4-15_RESERVED-Pad15)") (class "Default")
      (node (ref "U4") (pin "15") (pinfunction "15_RESERVED_15") (pintype "bidirectional"))
    )
    (net (code "111") (name "unconnected-(U4-16_RESERVED-Pad16)") (class "Default")
      (node (ref "U4") (pin "16") (pinfunction "16_RESERVED_16") (pintype "bidirectional"))
    )
    (net (code "112") (name "unconnected-(U4-17_RESERVED-Pad17)") (class "Default")
      (node (ref "U4") (pin "17") (pinfunction "17_RESERVED_17") (pintype "bidirectional"))
    )
    (net (code "113") (name "unconnected-(U4-20_TXD{slash}SPI_MISO-Pad20)") (class "Default")
      (node (ref "U4") (pin "20") (pinfunction "20_TXD/SPI_MISO_20") (pintype "bidirectional"))
    )
    (net (code "114") (name "unconnected-(U4-21_RXD{slash}SPI_MOSI-Pad21)") (class "Default")
      (node (ref "U4") (pin "21") (pinfunction "21_RXD/SPI_MOSI_21") (pintype "bidirectional"))
    )
  )
)
